# power_electronicsV4_3.net
KiCad netlist of a schematic drawn in EAGLE
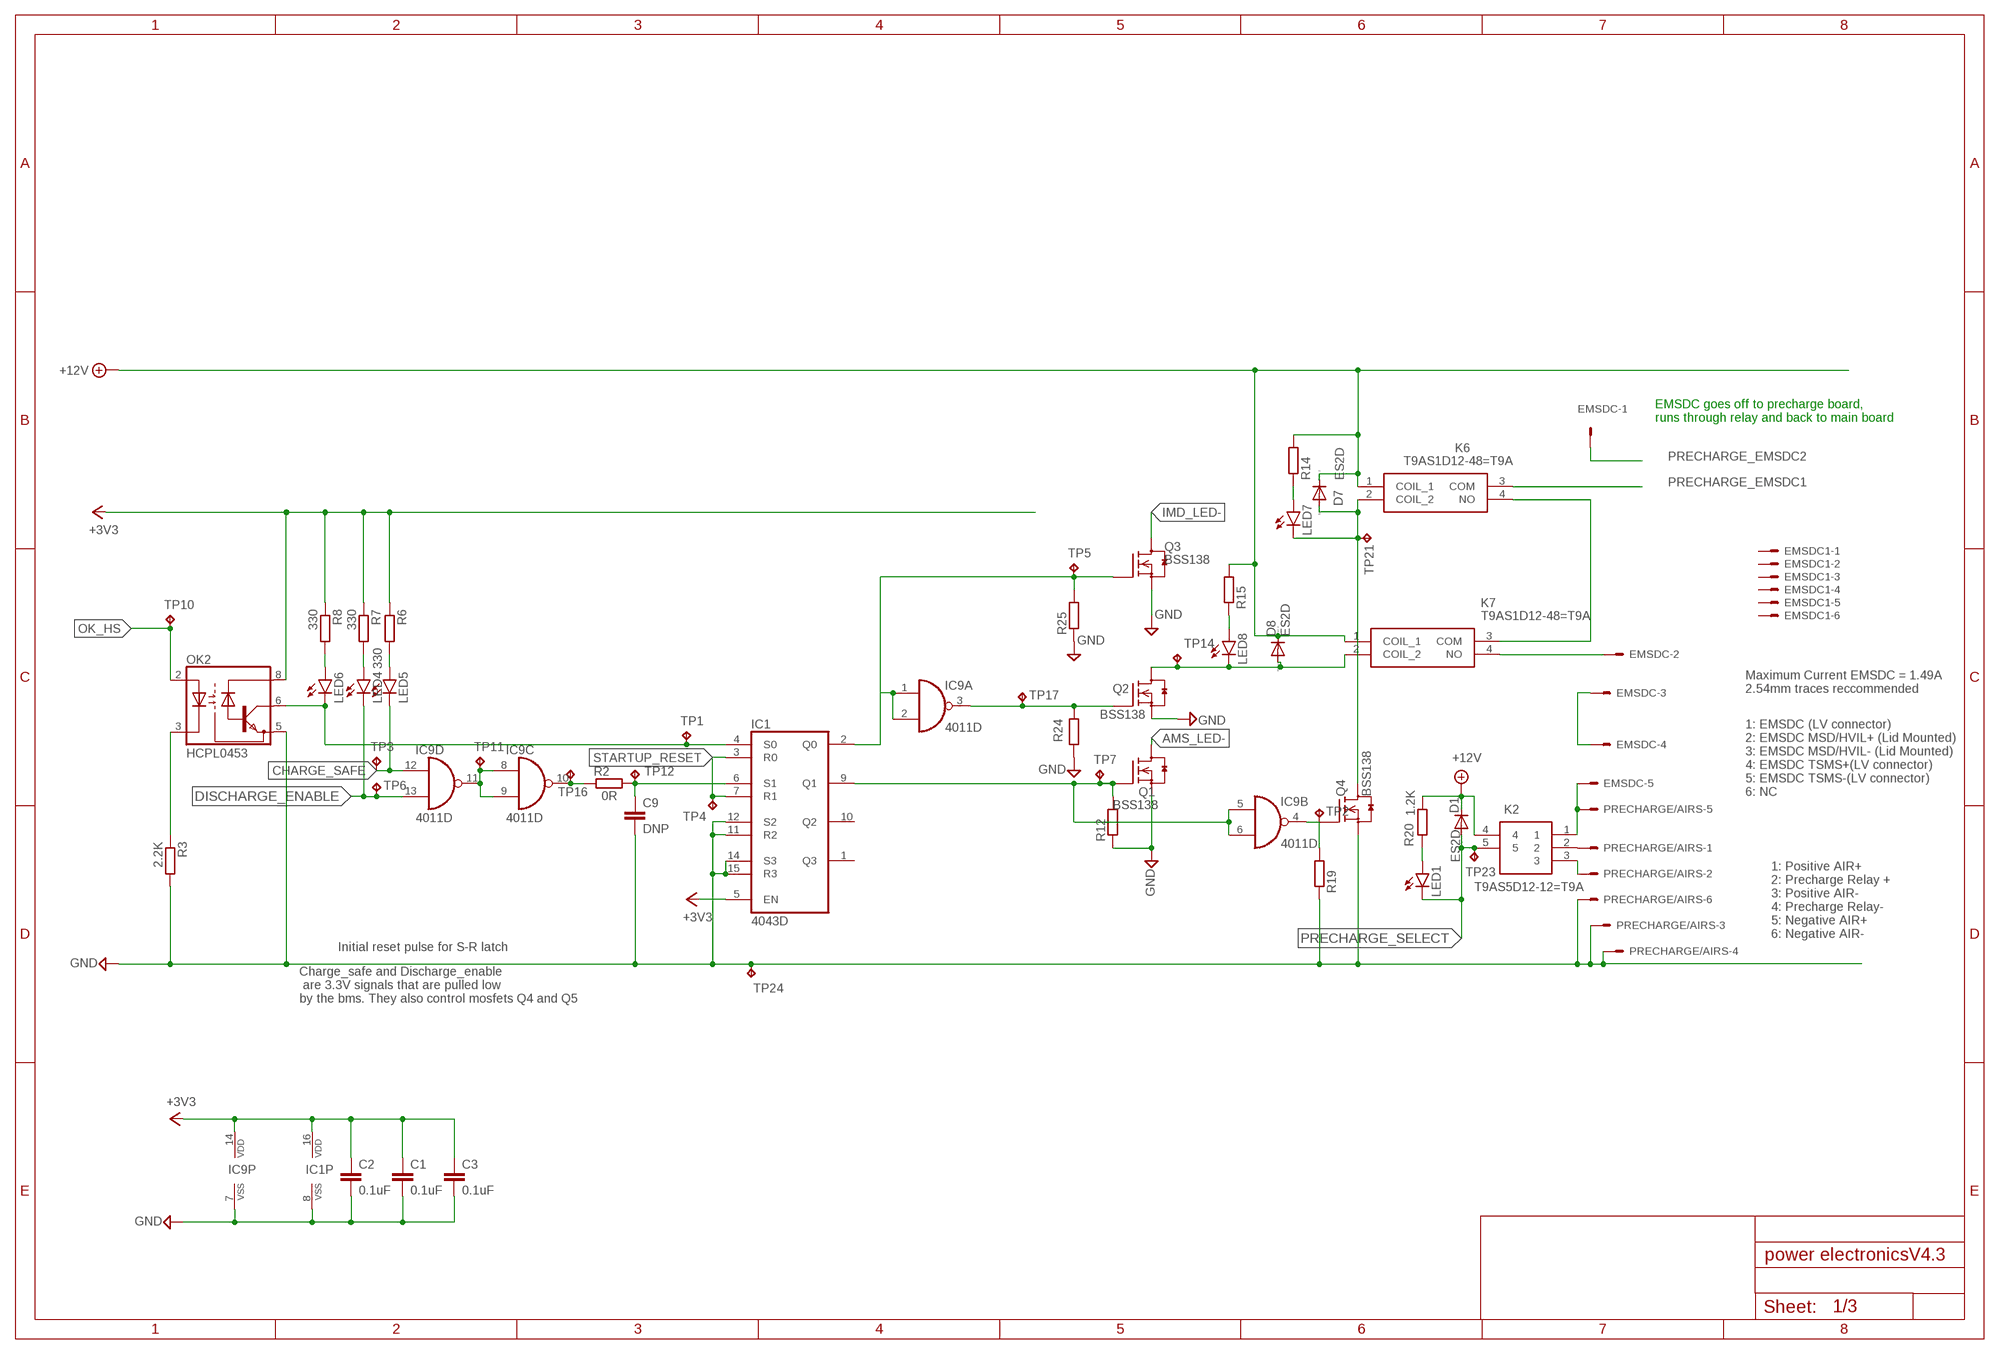
[diagram p0: schematic, sheet 1]
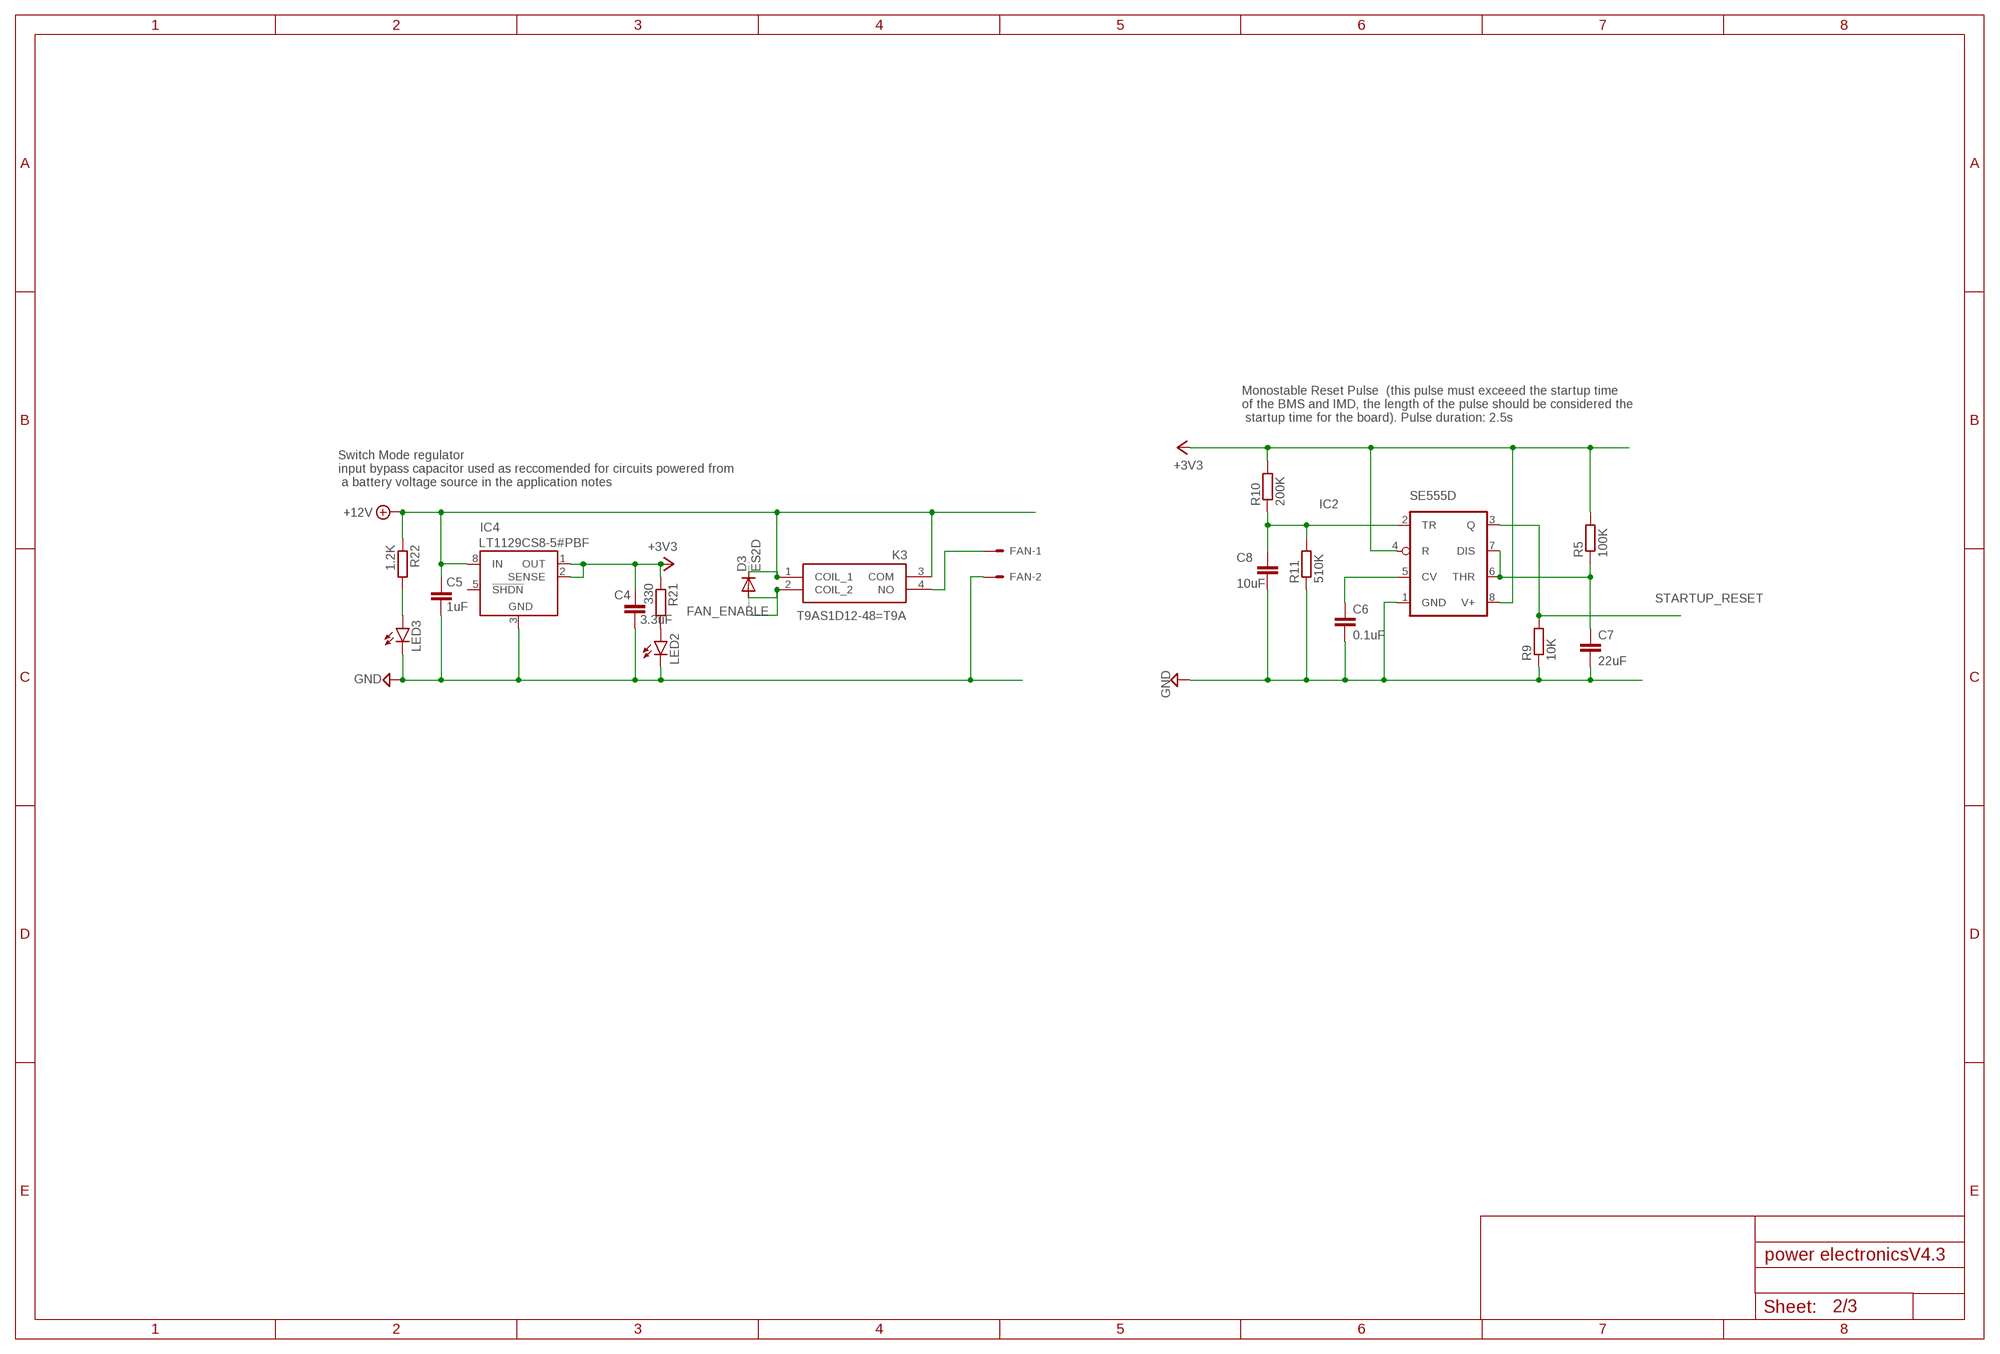
[diagram p1: schematic, sheet 2]
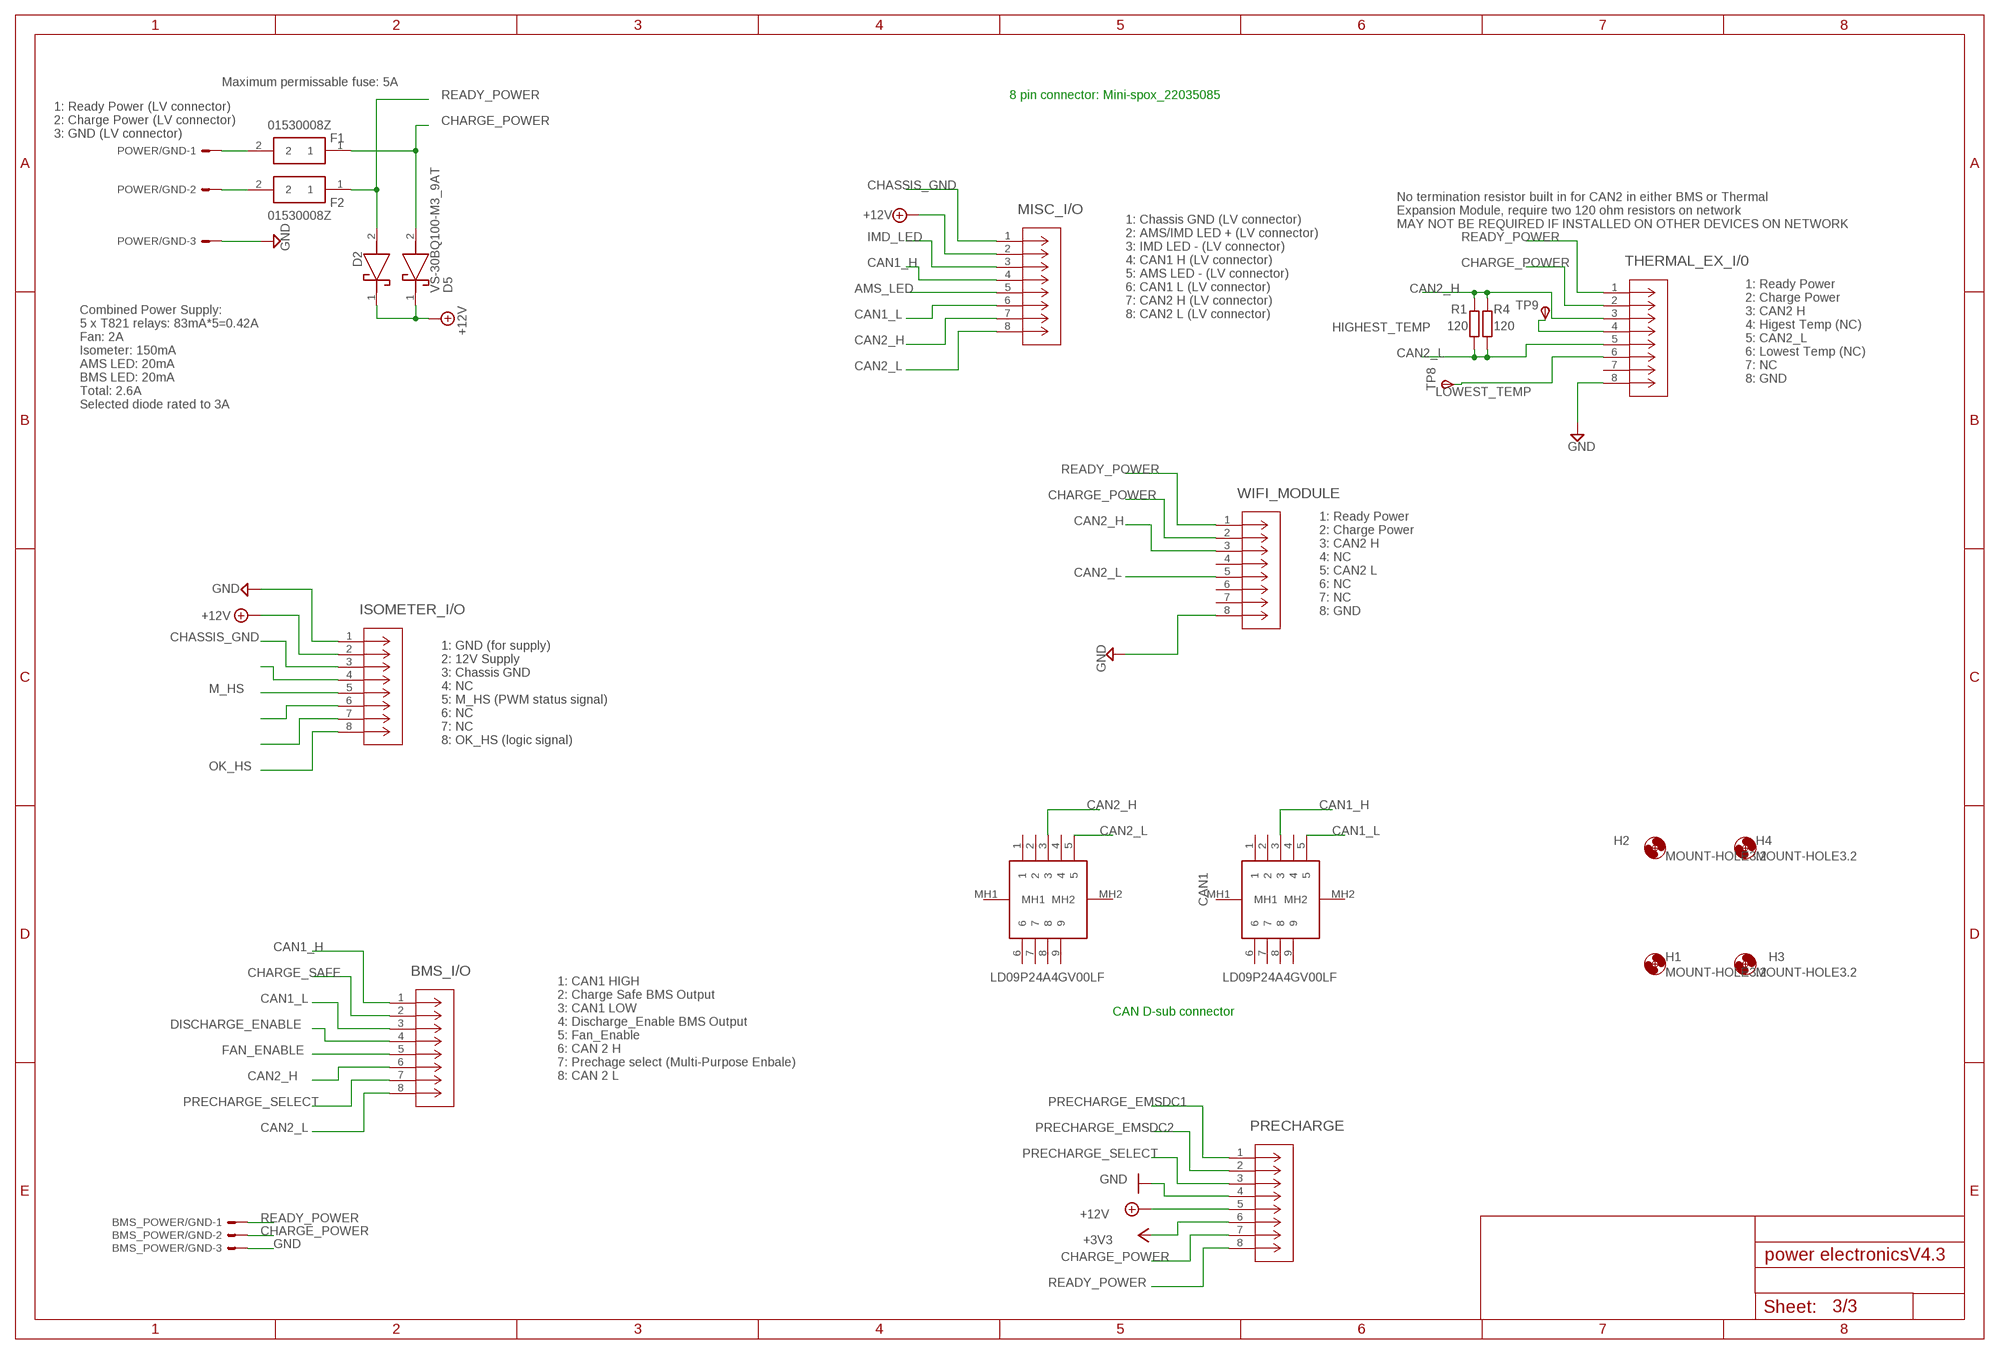
[diagram p2: schematic, sheet 3]

(export (version "E")
  (design (tool "Eeschema 10.0.6"))
  (components
    (comp (ref "C4")
      (value "3.3uF")
      (footprint "eagle-import:C0805")
      (libsource (lib "eagle-import") (part "C-EUC0805"))
    )
    (comp (ref "C5")
      (value "1uF")
      (footprint "eagle-import:C0805")
      (libsource (lib "eagle-import") (part "C-EUC0805"))
    )
    (comp (ref "C6")
      (value "0.1uF")
      (footprint "eagle-import:C0805")
      (libsource (lib "eagle-import") (part "C-EUC0805"))
    )
    (comp (ref "C7")
      (value "22uF")
      (footprint "eagle-import:C1206")
      (libsource (lib "eagle-import") (part "C-EUC1206"))
    )
    (comp (ref "C8")
      (value "10uF")
      (footprint "eagle-import:C0805")
      (libsource (lib "eagle-import") (part "C-EUC0805"))
    )
    (comp (ref "D3")
      (value "ES2D")
      (footprint "eagle-import:SMB")
      (libsource (lib "eagle-import") (part "ES2D"))
    )
    (comp (ref "FAN")
      (value "KK-156-2")
      (footprint "eagle-import:KK-156-2")
      (fields (field (name "MF") "MOLEX"))
      (libsource (lib "eagle-import") (part "KK-156-2"))
    )
    (comp (ref "IC2")
      (value "SE555D")
      (footprint "eagle-import:SO08")
      (libsource (lib "eagle-import") (part "555DSE"))
    )
    (comp (ref "IC4")
      (value "LT1129CS8")
      (footprint "eagle-import:SOIC8")
      (fields (field (name "MPN") "LT1129CS8-5#PBF"))
      (libsource (lib "eagle-import") (part "LT1129CS8"))
    )
    (comp (ref "K3")
      (value "T9AS1D12-48=T9A")
      (footprint "eagle-import:T9AS1D1248T9A")
      (fields (field (name "RS_PART_NUMBER") "6802534P"))
      (libsource (lib "eagle-import") (part "T9AS1D12-48=T9A"))
    )
    (comp (ref "LED2")
      (value "LEDSML0805")
      (footprint "eagle-import:SML0805")
      (libsource (lib "eagle-import") (part "LEDSML0805"))
    )
    (comp (ref "LED3")
      (value "LEDSML0805")
      (footprint "eagle-import:SML0805")
      (libsource (lib "eagle-import") (part "LEDSML0805"))
    )
    (comp (ref "R5")
      (value "100K")
      (footprint "eagle-import:R0805")
      (libsource (lib "eagle-import") (part "R-EU_R0805"))
    )
    (comp (ref "R9")
      (value "10K")
      (footprint "eagle-import:R0805")
      (libsource (lib "eagle-import") (part "R-EU_R0805"))
    )
    (comp (ref "R10")
      (value "200K")
      (footprint "eagle-import:R0805")
      (libsource (lib "eagle-import") (part "R-EU_R0805"))
    )
    (comp (ref "R11")
      (value "510K")
      (footprint "eagle-import:R0805")
      (libsource (lib "eagle-import") (part "R-EU_R0805"))
    )
    (comp (ref "R21")
      (value "330")
      (footprint "eagle-import:R0805")
      (libsource (lib "eagle-import") (part "R-EU_R0805"))
    )
    (comp (ref "R22")
      (value "1.2K")
      (footprint "eagle-import:R0805")
      (libsource (lib "eagle-import") (part "R-EU_R0805"))
    )
    (comp (ref "C1")
      (value "0.1uF")
      (footprint "eagle-import:C0805")
      (libsource (lib "eagle-import") (part "C-EUC0805"))
    )
    (comp (ref "C2")
      (value "0.1uF")
      (footprint "eagle-import:C0805")
      (libsource (lib "eagle-import") (part "C-EUC0805"))
    )
    (comp (ref "C3")
      (value "0.1uF")
      (footprint "eagle-import:C0805")
      (libsource (lib "eagle-import") (part "C-EUC0805"))
    )
    (comp (ref "C9")
      (value "DNP")
      (footprint "eagle-import:C0805K")
      (libsource (lib "eagle-import") (part "C-EUC0805K"))
    )
    (comp (ref "D1")
      (value "ES2D")
      (footprint "eagle-import:SMB")
      (libsource (lib "eagle-import") (part "ES2D"))
    )
    (comp (ref "D7")
      (value "ES2D")
      (footprint "eagle-import:SMB")
      (libsource (lib "eagle-import") (part "ES2D"))
    )
    (comp (ref "D8")
      (value "ES2D")
      (footprint "eagle-import:SMB")
      (libsource (lib "eagle-import") (part "ES2D"))
    )
    (comp (ref "EMSDC")
      (value "KK-156-6")
      (footprint "eagle-import:KK-156-6")
      (fields (field (name "MF") "MOLEX"))
      (libsource (lib "eagle-import") (part "KK-156-6"))
    )
    (comp (ref "EMSDC1")
      (value "KK-156-6")
      (footprint "eagle-import:KK-156-6")
      (fields (field (name "MF") "MOLEX"))
      (libsource (lib "eagle-import") (part "KK-156-6"))
    )
    (comp (ref "IC1")
      (value "4043D")
      (footprint "eagle-import:SO16")
      (libsource (lib "eagle-import") (part "4043D"))
    )
    (comp (ref "IC9")
      (value "4011D")
      (footprint "eagle-import:SO14")
      (libsource (lib "eagle-import") (part "4011D"))
    )
    (comp (ref "K2")
      (value "T9AS5D12-12=T9A")
      (footprint "eagle-import:T9AS1D12")
      (fields (field (name "RS_PART_NUMBER") "6802528"))
      (libsource (lib "eagle-import") (part "T9AS5D12-12=T9A"))
    )
    (comp (ref "K6")
      (value "T9AS1D12-48=T9A")
      (footprint "eagle-import:T9AS1D1248T9A")
      (libsource (lib "eagle-import") (part "T9AS1D12-12=T9A_T9AS1D12-48=T9A"))
    )
    (comp (ref "K7")
      (value "T9AS1D12-48=T9A")
      (footprint "eagle-import:T9AS1D1248T9A")
      (libsource (lib "eagle-import") (part "T9AS1D12-12=T9A_T9AS1D12-48=T9A"))
    )
    (comp (ref "LED1")
      (value "LEDSML0805")
      (footprint "eagle-import:SML0805")
      (libsource (lib "eagle-import") (part "LEDSML0805"))
    )
    (comp (ref "LED4")
      (value "LEDSML0805")
      (footprint "eagle-import:SML0805")
      (libsource (lib "eagle-import") (part "LEDSML0805"))
    )
    (comp (ref "LED5")
      (value "LEDSML0805")
      (footprint "eagle-import:SML0805")
      (libsource (lib "eagle-import") (part "LEDSML0805"))
    )
    (comp (ref "LED6")
      (value "LEDSML0805")
      (footprint "eagle-import:SML0805")
      (libsource (lib "eagle-import") (part "LEDSML0805"))
    )
    (comp (ref "LED7")
      (value "LEDSML0805")
      (footprint "eagle-import:SML0805")
      (libsource (lib "eagle-import") (part "LEDSML0805"))
    )
    (comp (ref "LED8")
      (value "LEDSML0805")
      (footprint "eagle-import:SML0805")
      (libsource (lib "eagle-import") (part "LEDSML0805"))
    )
    (comp (ref "OK2")
      (value "HCPL0453")
      (footprint "eagle-import:SOIC08")
      (fields (field (name "MF") "AGILENT TECHNOLOGIES") (field (name "MPN") "HCPL-0453-000E"))
      (libsource (lib "eagle-import") (part "HCPL0453"))
    )
    (comp (ref "PRECHARGE/AIRS")
      (value "KK-156-6")
      (footprint "eagle-import:KK-156-6")
      (fields (field (name "MF") "MOLEX"))
      (libsource (lib "eagle-import") (part "KK-156-6"))
    )
    (comp (ref "Q1")
      (value "BSS138")
      (footprint "eagle-import:SOT23")
      (libsource (lib "eagle-import") (part "BSS138"))
    )
    (comp (ref "Q2")
      (value "BSS138")
      (footprint "eagle-import:SOT23")
      (libsource (lib "eagle-import") (part "BSS138"))
    )
    (comp (ref "Q3")
      (value "BSS138")
      (footprint "eagle-import:SOT23")
      (libsource (lib "eagle-import") (part "BSS138"))
    )
    (comp (ref "Q4")
      (value "BSS138")
      (footprint "eagle-import:SOT23")
      (libsource (lib "eagle-import") (part "BSS138"))
    )
    (comp (ref "R2")
      (value "0R")
      (footprint "eagle-import:R0805")
      (libsource (lib "eagle-import") (part "R-EU_R0805"))
    )
    (comp (ref "R3")
      (value "2.2K")
      (footprint "eagle-import:R0805")
      (libsource (lib "eagle-import") (part "R-EU_R0805"))
    )
    (comp (ref "R6")
      (value "330")
      (footprint "eagle-import:R0805")
      (libsource (lib "eagle-import") (part "R-EU_R0805"))
    )
    (comp (ref "R7")
      (value "330")
      (footprint "eagle-import:R0805")
      (libsource (lib "eagle-import") (part "R-EU_R0805"))
    )
    (comp (ref "R8")
      (value "330")
      (footprint "eagle-import:R0805")
      (libsource (lib "eagle-import") (part "R-EU_R0805"))
    )
    (comp (ref "R12")
      (value "R-EU_R0805")
      (footprint "eagle-import:R0805")
      (libsource (lib "eagle-import") (part "R-EU_R0805"))
    )
    (comp (ref "R14")
      (value "R-EU_R0805")
      (footprint "eagle-import:R0805")
      (libsource (lib "eagle-import") (part "R-EU_R0805"))
    )
    (comp (ref "R15")
      (value "R-EU_R0805")
      (footprint "eagle-import:R0805")
      (libsource (lib "eagle-import") (part "R-EU_R0805"))
    )
    (comp (ref "R19")
      (value "R-EU_R0805")
      (footprint "eagle-import:R0805")
      (libsource (lib "eagle-import") (part "R-EU_R0805"))
    )
    (comp (ref "R20")
      (value "1.2K")
      (footprint "eagle-import:R0805")
      (libsource (lib "eagle-import") (part "R-EU_R0805"))
    )
    (comp (ref "R24")
      (value "R-EU_R0805")
      (footprint "eagle-import:R0805")
      (libsource (lib "eagle-import") (part "R-EU_R0805"))
    )
    (comp (ref "R25")
      (value "R-EU_R0805")
      (footprint "eagle-import:R0805")
      (libsource (lib "eagle-import") (part "R-EU_R0805"))
    )
    (comp (ref "TP1")
      (value "TPPAD1-17")
      (footprint "eagle-import:P1-17")
      (libsource (lib "eagle-import") (part "TPPAD1-17"))
    )
    (comp (ref "TP2")
      (value "TPPAD1-17")
      (footprint "eagle-import:P1-17")
      (libsource (lib "eagle-import") (part "TPPAD1-17"))
    )
    (comp (ref "TP3")
      (value "TPPAD1-17")
      (footprint "eagle-import:P1-17")
      (libsource (lib "eagle-import") (part "TPPAD1-17"))
    )
    (comp (ref "TP4")
      (value "TPPAD1-17")
      (footprint "eagle-import:P1-17")
      (libsource (lib "eagle-import") (part "TPPAD1-17"))
    )
    (comp (ref "TP5")
      (value "TPPAD1-17")
      (footprint "eagle-import:P1-17")
      (libsource (lib "eagle-import") (part "TPPAD1-17"))
    )
    (comp (ref "TP6")
      (value "TPPAD1-17")
      (footprint "eagle-import:P1-17")
      (libsource (lib "eagle-import") (part "TPPAD1-17"))
    )
    (comp (ref "TP7")
      (value "TPPAD1-17")
      (footprint "eagle-import:P1-17")
      (libsource (lib "eagle-import") (part "TPPAD1-17"))
    )
    (comp (ref "TP10")
      (value "TPPAD1-17")
      (footprint "eagle-import:P1-17")
      (libsource (lib "eagle-import") (part "TPPAD1-17"))
    )
    (comp (ref "TP11")
      (value "TPPAD1-17")
      (footprint "eagle-import:P1-17")
      (libsource (lib "eagle-import") (part "TPPAD1-17"))
    )
    (comp (ref "TP12")
      (value "TPPAD1-17")
      (footprint "eagle-import:P1-17")
      (libsource (lib "eagle-import") (part "TPPAD1-17"))
    )
    (comp (ref "TP14")
      (value "TPPAD1-17")
      (footprint "eagle-import:P1-17")
      (libsource (lib "eagle-import") (part "TPPAD1-17"))
    )
    (comp (ref "TP16")
      (value "TPPAD1-17")
      (footprint "eagle-import:P1-17")
      (libsource (lib "eagle-import") (part "TPPAD1-17"))
    )
    (comp (ref "TP17")
      (value "TPPAD1-17")
      (footprint "eagle-import:P1-17")
      (libsource (lib "eagle-import") (part "TPPAD1-17"))
    )
    (comp (ref "TP21")
      (value "TPPAD1-17")
      (footprint "eagle-import:P1-17")
      (libsource (lib "eagle-import") (part "TPPAD1-17"))
    )
    (comp (ref "TP23")
      (value "TPPAD1-17")
      (footprint "eagle-import:P1-17")
      (libsource (lib "eagle-import") (part "TPPAD1-17"))
    )
    (comp (ref "TP24")
      (value "TPPAD1-17")
      (footprint "eagle-import:P1-17")
      (libsource (lib "eagle-import") (part "TPPAD1-17"))
    )
    (comp (ref "BMS_I/O")
      (value "MINI-SPOX_22035085")
      (footprint "eagle-import:CON_22035085_MOL")
      (fields
        (field (name "MANUFACTURER_PART_NUMBER") "22035085")
        (field (name "COPYRIGHT") "Copyright (C) 2023 Ultra Librarian. All rights reserved.")
      )
      (libsource (lib "eagle-import") (part "MINI-SPOX_22035085"))
    )
    (comp (ref "BMS_POWER/GND")
      (value "KK-156-3")
      (footprint "eagle-import:KK-156-3")
      (fields (field (name "MF") "MOLEX"))
      (libsource (lib "eagle-import") (part "KK-156-3"))
    )
    (comp (ref "CAN1")
      (value "LD09P24A4GV00LF")
      (footprint "eagle-import:LD09P24A4GV00LF")
      (fields (field (name "MOUSER_PART_NUMBER") "649-LD09P24A4GV00LF"))
      (libsource (lib "eagle-import") (part "LD09P24A4GV00LF"))
    )
    (comp (ref "CAN2")
      (value "LD09P24A4GV00LF")
      (footprint "eagle-import:LD09P24A4GV00LF")
      (fields (field (name "MOUSER_PART_NUMBER") "649-LD09P24A4GV00LF"))
      (libsource (lib "eagle-import") (part "LD09P24A4GV00LF"))
    )
    (comp (ref "D2")
      (value "VS-30BQ100-M3_9AT")
      (footprint "eagle-import:DIOM7959X262N")
      (fields
        (field (name "MANUFACTURER_PART_NUMBER") "VS-30BQ100-M3/9AT")
        (field (name "MOUSER_PART_NUMBER") "78-VS-30BQ100-M39AT")
      )
      (libsource (lib "eagle-import") (part "VS-30BQ100-M3_9AT"))
    )
    (comp (ref "D5")
      (value "VS-30BQ100-M3_9AT")
      (footprint "eagle-import:DIOM7959X262N")
      (fields
        (field (name "MANUFACTURER_PART_NUMBER") "VS-30BQ100-M3/9AT")
        (field (name "MOUSER_PART_NUMBER") "78-VS-30BQ100-M39AT")
      )
      (libsource (lib "eagle-import") (part "VS-30BQ100-M3_9AT"))
    )
    (comp (ref "F1")
      (value "01530008Z")
      (footprint "eagle-import:01530008")
      (fields (field (name "RS_PART_NUMBER") "3607317"))
      (libsource (lib "eagle-import") (part "01530008Z"))
    )
    (comp (ref "F2")
      (value "01530008Z")
      (footprint "eagle-import:01530008")
      (fields (field (name "RS_PART_NUMBER") "3607317"))
      (libsource (lib "eagle-import") (part "01530008Z"))
    )
    (comp (ref "H1")
      (value "MOUNT-HOLE3.2")
      (footprint "eagle-import:3,2")
      (libsource (lib "eagle-import") (part "MOUNT-HOLE3.2"))
    )
    (comp (ref "H2")
      (value "MOUNT-HOLE3.2")
      (footprint "eagle-import:3,2")
      (libsource (lib "eagle-import") (part "MOUNT-HOLE3.2"))
    )
    (comp (ref "H3")
      (value "MOUNT-HOLE3.2")
      (footprint "eagle-import:3,2")
      (libsource (lib "eagle-import") (part "MOUNT-HOLE3.2"))
    )
    (comp (ref "H4")
      (value "MOUNT-HOLE3.2")
      (footprint "eagle-import:3,2")
      (libsource (lib "eagle-import") (part "MOUNT-HOLE3.2"))
    )
    (comp (ref "ISOMETER_I/O")
      (value "MINI-SPOX_22035085")
      (footprint "eagle-import:CON_22035085_MOL")
      (fields
        (field (name "MANUFACTURER_PART_NUMBER") "22035085")
        (field (name "COPYRIGHT") "Copyright (C) 2023 Ultra Librarian. All rights reserved.")
      )
      (libsource (lib "eagle-import") (part "MINI-SPOX_22035085"))
    )
    (comp (ref "MISC_I/O")
      (value "MINI-SPOX_22035085")
      (footprint "eagle-import:CON_22035085_MOL")
      (fields
        (field (name "MANUFACTURER_PART_NUMBER") "22035085")
        (field (name "COPYRIGHT") "Copyright (C) 2023 Ultra Librarian. All rights reserved.")
      )
      (libsource (lib "eagle-import") (part "MINI-SPOX_22035085"))
    )
    (comp (ref "POWER/GND")
      (value "KK-156-3")
      (footprint "eagle-import:KK-156-3")
      (fields (field (name "MF") "MOLEX"))
      (libsource (lib "eagle-import") (part "KK-156-3"))
    )
    (comp (ref "PRECHARGE")
      (value "MINI-SPOX_22035085")
      (footprint "eagle-import:CON_22035085_MOL")
      (fields
        (field (name "MANUFACTURER_PART_NUMBER") "22035085")
        (field (name "COPYRIGHT") "Copyright (C) 2023 Ultra Librarian. All rights reserved.")
      )
      (libsource (lib "eagle-import") (part "MINI-SPOX_22035085"))
    )
    (comp (ref "R1")
      (value "120")
      (footprint "eagle-import:R1206")
      (libsource (lib "eagle-import") (part "R-EU_R1206"))
    )
    (comp (ref "R4")
      (value "120")
      (footprint "eagle-import:R1206")
      (libsource (lib "eagle-import") (part "R-EU_R1206"))
    )
    (comp (ref "THERMAL_EX_I/0")
      (value "MINI-SPOX_22035085")
      (footprint "eagle-import:CON_22035085_MOL")
      (fields
        (field (name "MANUFACTURER_PART_NUMBER") "22035085")
        (field (name "COPYRIGHT") "Copyright (C) 2023 Ultra Librarian. All rights reserved.")
      )
      (libsource (lib "eagle-import") (part "MINI-SPOX_22035085"))
    )
    (comp (ref "TP8")
      (value "TPSTP11R")
      (footprint "eagle-import:TP11R")
      (libsource (lib "eagle-import") (part "TPSTP11R"))
    )
    (comp (ref "TP9")
      (value "TPSTP11R")
      (footprint "eagle-import:TP11R")
      (libsource (lib "eagle-import") (part "TPSTP11R"))
    )
    (comp (ref "WIFI_MODULE")
      (value "MINI-SPOX_22035085")
      (footprint "eagle-import:CON_22035085_MOL")
      (fields
        (field (name "MANUFACTURER_PART_NUMBER") "22035085")
        (field (name "COPYRIGHT") "Copyright (C) 2023 Ultra Librarian. All rights reserved.")
      )
      (libsource (lib "eagle-import") (part "MINI-SPOX_22035085"))
    )
  )
  (nets
    (net (code "1") (name "+3V3") (class "Default")
      (node (ref "C1") (pin "1") (pinfunction "1_1") (pintype "passive"))
      (node (ref "C2") (pin "1") (pinfunction "1_1") (pintype "passive"))
      (node (ref "C3") (pin "1") (pinfunction "1_1") (pintype "passive"))
      (node (ref "C4") (pin "1") (pinfunction "1_1") (pintype "passive"))
      (node (ref "IC1") (pin "16") (pinfunction "VDD_16") (pintype "power_in"))
      (node (ref "IC1") (pin "5") (pinfunction "EN_5") (pintype "input"))
      (node (ref "IC2") (pin "4") (pinfunction "R_4") (pintype "input"))
      (node (ref "IC2") (pin "8") (pinfunction "V+_8") (pintype "power_in"))
      (node (ref "IC4") (pin "1") (pinfunction "OUT_1") (pintype "output"))
      (node (ref "IC4") (pin "2") (pinfunction "SENSE_2") (pintype "input"))
      (node (ref "IC9") (pin "14") (pinfunction "VDD_14") (pintype "power_in"))
      (node (ref "OK2") (pin "8") (pinfunction "VCC_8") (pintype "passive"))
      (node (ref "PRECHARGE") (pin "6") (pinfunction "6_6") (pintype "passive"))
      (node (ref "R10") (pin "2") (pinfunction "2_2") (pintype "passive"))
      (node (ref "R21") (pin "1") (pinfunction "1_1") (pintype "passive"))
      (node (ref "R5") (pin "2") (pinfunction "2_2") (pintype "passive"))
      (node (ref "R6") (pin "1") (pinfunction "1_1") (pintype "passive"))
      (node (ref "R7") (pin "1") (pinfunction "1_1") (pintype "passive"))
      (node (ref "R8") (pin "1") (pinfunction "1_1") (pintype "passive"))
    )
    (net (code "2") (name "+12V") (class "Default")
      (node (ref "C5") (pin "1") (pinfunction "1_1") (pintype "passive"))
      (node (ref "D1") (pin "C") (pinfunction "C_C") (pintype "passive"))
      (node (ref "D2") (pin "1") (pinfunction "K_1") (pintype "bidirectional"))
      (node (ref "D3") (pin "C") (pinfunction "C_C") (pintype "passive"))
      (node (ref "D5") (pin "1") (pinfunction "K_1") (pintype "bidirectional"))
      (node (ref "D7") (pin "C") (pinfunction "C_C") (pintype "passive"))
      (node (ref "D8") (pin "C") (pinfunction "C_C") (pintype "passive"))
      (node (ref "IC4") (pin "8") (pinfunction "IN_8") (pintype "input"))
      (node (ref "ISOMETER_I/O") (pin "2") (pinfunction "2_2") (pintype "passive"))
      (node (ref "K2") (pin "4") (pinfunction "4_4") (pintype "bidirectional"))
      (node (ref "K3") (pin "1") (pinfunction "COIL_1_1") (pintype "bidirectional"))
      (node (ref "K3") (pin "3") (pinfunction "COM_3") (pintype "bidirectional"))
      (node (ref "K6") (pin "1") (pinfunction "COIL_1_1") (pintype "bidirectional"))
      (node (ref "K7") (pin "1") (pinfunction "COIL_1_1") (pintype "bidirectional"))
      (node (ref "MISC_I/O") (pin "2") (pinfunction "2_2") (pintype "passive"))
      (node (ref "PRECHARGE") (pin "5") (pinfunction "5_5") (pintype "passive"))
      (node (ref "R14") (pin "2") (pinfunction "2_2") (pintype "passive"))
      (node (ref "R15") (pin "2") (pinfunction "2_2") (pintype "passive"))
      (node (ref "R20") (pin "1") (pinfunction "1_1") (pintype "passive"))
      (node (ref "R22") (pin "1") (pinfunction "1_1") (pintype "passive"))
    )
    (net (code "3") (name "AMS_LED") (class "Default")
      (node (ref "MISC_I/O") (pin "5") (pinfunction "5_5") (pintype "passive"))
    )
    (net (code "4") (name "AMS_LED-") (class "Default")
      (node (ref "Q1") (pin "3") (pinfunction "D_3") (pintype "passive"))
    )
    (net (code "5") (name "CAN1_H") (class "Default")
      (node (ref "BMS_I/O") (pin "1") (pinfunction "1_1") (pintype "passive"))
      (node (ref "CAN1") (pin "3") (pinfunction "3_3") (pintype "bidirectional"))
      (node (ref "MISC_I/O") (pin "4") (pinfunction "4_4") (pintype "passive"))
    )
    (net (code "6") (name "CAN1_L") (class "Default")
      (node (ref "BMS_I/O") (pin "3") (pinfunction "3_3") (pintype "passive"))
      (node (ref "CAN1") (pin "5") (pinfunction "5_5") (pintype "bidirectional"))
      (node (ref "MISC_I/O") (pin "6") (pinfunction "6_6") (pintype "passive"))
    )
    (net (code "7") (name "CAN2_H") (class "Default")
      (node (ref "BMS_I/O") (pin "6") (pinfunction "6_6") (pintype "passive"))
      (node (ref "CAN2") (pin "3") (pinfunction "3_3") (pintype "bidirectional"))
      (node (ref "MISC_I/O") (pin "7") (pinfunction "7_7") (pintype "passive"))
      (node (ref "R1") (pin "1") (pinfunction "1_1") (pintype "passive"))
      (node (ref "R4") (pin "1") (pinfunction "1_1") (pintype "passive"))
      (node (ref "THERMAL_EX_I/0") (pin "3") (pinfunction "3_3") (pintype "passive"))
      (node (ref "WIFI_MODULE") (pin "3") (pinfunction "3_3") (pintype "passive"))
    )
    (net (code "8") (name "CAN2_L") (class "Default")
      (node (ref "BMS_I/O") (pin "8") (pinfunction "8_8") (pintype "passive"))
      (node (ref "CAN2") (pin "5") (pinfunction "5_5") (pintype "bidirectional"))
      (node (ref "MISC_I/O") (pin "8") (pinfunction "8_8") (pintype "passive"))
      (node (ref "R1") (pin "2") (pinfunction "2_2") (pintype "passive"))
      (node (ref "R4") (pin "2") (pinfunction "2_2") (pintype "passive"))
      (node (ref "THERMAL_EX_I/0") (pin "5") (pinfunction "5_5") (pintype "passive"))
      (node (ref "WIFI_MODULE") (pin "5") (pinfunction "5_5") (pintype "passive"))
    )
    (net (code "9") (name "CHARGE_POWER") (class "Default")
      (node (ref "BMS_POWER/GND") (pin "2") (pinfunction "S_2") (pintype "passive"))
      (node (ref "D5") (pin "2") (pinfunction "A_2") (pintype "bidirectional"))
      (node (ref "F1") (pin "1") (pinfunction "1_1") (pintype "bidirectional"))
      (node (ref "PRECHARGE") (pin "7") (pinfunction "7_7") (pintype "passive"))
      (node (ref "THERMAL_EX_I/0") (pin "2") (pinfunction "2_2") (pintype "passive"))
      (node (ref "WIFI_MODULE") (pin "2") (pinfunction "2_2") (pintype "passive"))
    )
    (net (code "10") (name "CHARGE_SAFE") (class "Default")
      (node (ref "BMS_I/O") (pin "2") (pinfunction "2_2") (pintype "passive"))
      (node (ref "IC9") (pin "12") (pinfunction "I0_12") (pintype "input"))
      (node (ref "LED5") (pin "C") (pinfunction "C_C") (pintype "passive"))
      (node (ref "TP3") (pin "TP") (pinfunction "TP_TP") (pintype "input"))
    )
    (net (code "11") (name "CHASSIS_GND") (class "Default")
      (node (ref "ISOMETER_I/O") (pin "3") (pinfunction "3_3") (pintype "passive"))
      (node (ref "MISC_I/O") (pin "1") (pinfunction "1_1") (pintype "passive"))
    )
    (net (code "12") (name "DISCHARGE_ENABLE") (class "Default")
      (node (ref "BMS_I/O") (pin "4") (pinfunction "4_4") (pintype "passive"))
      (node (ref "IC1") (pin "9") (pinfunction "Q1_9") (pintype "output"))
      (node (ref "IC9") (pin "13") (pinfunction "I1_13") (pintype "input"))
      (node (ref "IC9") (pin "5") (pinfunction "I0_5") (pintype "input"))
      (node (ref "IC9") (pin "6") (pinfunction "I1_6") (pintype "input"))
      (node (ref "LED4") (pin "C") (pinfunction "C_C") (pintype "passive"))
      (node (ref "Q1") (pin "1") (pinfunction "G_1") (pintype "passive"))
      (node (ref "R12") (pin "2") (pinfunction "2_2") (pintype "passive"))
      (node (ref "TP6") (pin "TP") (pinfunction "TP_TP") (pintype "input"))
      (node (ref "TP7") (pin "TP") (pinfunction "TP_TP") (pintype "input"))
    )
    (net (code "13") (name "FAN_ENABLE") (class "Default")
      (node (ref "BMS_I/O") (pin "5") (pinfunction "5_5") (pintype "passive"))
      (node (ref "D3") (pin "A") (pinfunction "A_A") (pintype "passive"))
      (node (ref "K3") (pin "2") (pinfunction "COIL_2_2") (pintype "bidirectional"))
    )
    (net (code "14") (name "GND") (class "Default")
      (node (ref "BMS_POWER/GND") (pin "3") (pinfunction "S_3") (pintype "passive"))
      (node (ref "C1") (pin "2") (pinfunction "2_2") (pintype "passive"))
      (node (ref "C2") (pin "2") (pinfunction "2_2") (pintype "passive"))
      (node (ref "C3") (pin "2") (pinfunction "2_2") (pintype "passive"))
      (node (ref "C4") (pin "2") (pinfunction "2_2") (pintype "passive"))
      (node (ref "C5") (pin "2") (pinfunction "2_2") (pintype "passive"))
      (node (ref "C6") (pin "2") (pinfunction "2_2") (pintype "passive"))
      (node (ref "C7") (pin "2") (pinfunction "2_2") (pintype "passive"))
      (node (ref "C8") (pin "2") (pinfunction "2_2") (pintype "passive"))
      (node (ref "C9") (pin "2") (pinfunction "2_2") (pintype "passive"))
      (node (ref "FAN") (pin "2") (pinfunction "S_2") (pintype "passive"))
      (node (ref "IC1") (pin "11") (pinfunction "R2_11") (pintype "input"))
      (node (ref "IC1") (pin "12") (pinfunction "S2_12") (pintype "input"))
      (node (ref "IC1") (pin "14") (pinfunction "S3_14") (pintype "input"))
      (node (ref "IC1") (pin "15") (pinfunction "R3_15") (pintype "input"))
      (node (ref "IC1") (pin "8") (pinfunction "VSS_8") (pintype "power_in"))
      (node (ref "IC2") (pin "1") (pinfunction "GND_1") (pintype "power_in"))
      (node (ref "IC4") (pin "3") (pinfunction "GND_3") (pintype "power_in"))
      (node (ref "IC9") (pin "7") (pinfunction "VSS_7") (pintype "power_in"))
      (node (ref "ISOMETER_I/O") (pin "1") (pinfunction "1_1") (pintype "passive"))
      (node (ref "LED2") (pin "C") (pinfunction "C_C") (pintype "passive"))
      (node (ref "LED3") (pin "C") (pinfunction "C_C") (pintype "passive"))
      (node (ref "OK2") (pin "5") (pinfunction "GND_5") (pintype "passive"))
      (node (ref "POWER/GND") (pin "3") (pinfunction "S_3") (pintype "passive"))
      (node (ref "PRECHARGE") (pin "4") (pinfunction "4_4") (pintype "passive"))
      (node (ref "PRECHARGE/AIRS") (pin "3") (pinfunction "S_3") (pintype "passive"))
      (node (ref "PRECHARGE/AIRS") (pin "4") (pinfunction "S_4") (pintype "passive"))
      (node (ref "PRECHARGE/AIRS") (pin "6") (pinfunction "S_6") (pintype "passive"))
      (node (ref "Q1") (pin "2") (pinfunction "S_2") (pintype "passive"))
      (node (ref "Q2") (pin "2") (pinfunction "S_2") (pintype "passive"))
      (node (ref "Q3") (pin "2") (pinfunction "S_2") (pintype "passive"))
      (node (ref "Q4") (pin "2") (pinfunction "S_2") (pintype "passive"))
      (node (ref "R11") (pin "1") (pinfunction "1_1") (pintype "passive"))
      (node (ref "R12") (pin "1") (pinfunction "1_1") (pintype "passive"))
      (node (ref "R19") (pin "1") (pinfunction "1_1") (pintype "passive"))
      (node (ref "R24") (pin "1") (pinfunction "1_1") (pintype "passive"))
      (node (ref "R25") (pin "1") (pinfunction "1_1") (pintype "passive"))
      (node (ref "R3") (pin "2") (pinfunction "2_2") (pintype "passive"))
      (node (ref "R9") (pin "1") (pinfunction "1_1") (pintype "passive"))
      (node (ref "THERMAL_EX_I/0") (pin "8") (pinfunction "8_8") (pintype "passive"))
      (node (ref "TP24") (pin "TP") (pinfunction "TP_TP") (pintype "input"))
      (node (ref "WIFI_MODULE") (pin "8") (pinfunction "8_8") (pintype "passive"))
    )
    (net (code "15") (name "HIGHEST_TEMP") (class "Default")
      (node (ref "THERMAL_EX_I/0") (pin "4") (pinfunction "4_4") (pintype "passive"))
      (node (ref "TP9") (pin "TP") (pinfunction "PP_TP") (pintype "input"))
    )
    (net (code "16") (name "IMD_LED") (class "Default")
      (node (ref "MISC_I/O") (pin "3") (pinfunction "3_3") (pintype "passive"))
    )
    (net (code "17") (name "IMD_LED-") (class "Default")
      (node (ref "Q3") (pin "3") (pinfunction "D_3") (pintype "passive"))
    )
    (net (code "18") (name "LOWEST_TEMP") (class "Default")
      (node (ref "THERMAL_EX_I/0") (pin "6") (pinfunction "6_6") (pintype "passive"))
      (node (ref "TP8") (pin "TP") (pinfunction "PP_TP") (pintype "input"))
    )
    (net (code "19") (name "M_HS") (class "Default")
      (node (ref "ISOMETER_I/O") (pin "5") (pinfunction "5_5") (pintype "passive"))
    )
    (net (code "20") (name "Net-(EMSDCB-S)") (class "Default")
      (node (ref "EMSDC") (pin "2") (pinfunction "S_2") (pintype "passive"))
      (node (ref "K7") (pin "4") (pinfunction "NO_4") (pintype "bidirectional"))
    )
    (net (code "21") (name "Net-(EMSDCC-S)") (class "Default")
      (node (ref "EMSDC") (pin "3") (pinfunction "S_3") (pintype "passive"))
      (node (ref "EMSDC") (pin "4") (pinfunction "S_4") (pintype "passive"))
    )
    (net (code "22") (name "Net-(EMSDCE-S)") (class "Default")
      (node (ref "EMSDC") (pin "5") (pinfunction "S_5") (pintype "passive"))
      (node (ref "K2") (pin "1") (pinfunction "1_1") (pintype "bidirectional"))
      (node (ref "PRECHARGE/AIRS") (pin "5") (pinfunction "S_5") (pintype "passive"))
    )
    (net (code "23") (name "Net-(FANA-S)") (class "Default")
      (node (ref "FAN") (pin "1") (pinfunction "S_1") (pintype "passive"))
      (node (ref "K3") (pin "4") (pinfunction "NO_4") (pintype "bidirectional"))
    )
    (net (code "24") (name "Net-(IC1A-Q0)") (class "Default")
      (node (ref "IC1") (pin "2") (pinfunction "Q0_2") (pintype "output"))
      (node (ref "IC9") (pin "1") (pinfunction "I0_1") (pintype "input"))
      (node (ref "IC9") (pin "2") (pinfunction "I1_2") (pintype "input"))
      (node (ref "Q3") (pin "1") (pinfunction "G_1") (pintype "passive"))
      (node (ref "R25") (pin "2") (pinfunction "2_2") (pintype "passive"))
      (node (ref "TP5") (pin "TP") (pinfunction "TP_TP") (pintype "input"))
    )
    (net (code "25") (name "Net-(IC1A-S0)") (class "Default")
      (node (ref "IC1") (pin "4") (pinfunction "S0_4") (pintype "input"))
      (node (ref "LED6") (pin "C") (pinfunction "C_C") (pintype "passive"))
      (node (ref "OK2") (pin "6") (pinfunction "VO_6") (pintype "passive"))
      (node (ref "TP1") (pin "TP") (pinfunction "TP_TP") (pintype "input"))
    )
    (net (code "26") (name "Net-(IC1A-S1)") (class "Default")
      (node (ref "C9") (pin "1") (pinfunction "1_1") (pintype "passive"))
      (node (ref "IC1") (pin "6") (pinfunction "S1_6") (pintype "input"))
      (node (ref "R2") (pin "2") (pinfunction "2_2") (pintype "passive"))
      (node (ref "TP12") (pin "TP") (pinfunction "TP_TP") (pintype "input"))
    )
    (net (code "27") (name "Net-(IC2-CV)") (class "Default")
      (node (ref "C6") (pin "1") (pinfunction "1_1") (pintype "passive"))
      (node (ref "IC2") (pin "5") (pinfunction "CV_5") (pintype "input"))
    )
    (net (code "28") (name "Net-(IC2-DIS)") (class "Default")
      (node (ref "C7") (pin "1") (pinfunction "1_1") (pintype "passive"))
      (node (ref "IC2") (pin "6") (pinfunction "THR_6") (pintype "input"))
      (node (ref "IC2") (pin "7") (pinfunction "DIS_7") (pintype "input"))
      (node (ref "R5") (pin "1") (pinfunction "1_1") (pintype "passive"))
    )
    (net (code "29") (name "Net-(IC2-TR)") (class "Default")
      (node (ref "C8") (pin "1") (pinfunction "1_1") (pintype "passive"))
      (node (ref "IC2") (pin "2") (pinfunction "TR_2") (pintype "input"))
      (node (ref "R10") (pin "1") (pinfunction "1_1") (pintype "passive"))
      (node (ref "R11") (pin "2") (pinfunction "2_2") (pintype "passive"))
    )
    (net (code "30") (name "Net-(IC9A-O)") (class "Default")
      (node (ref "IC9") (pin "3") (pinfunction "O_3") (pintype "output"))
      (node (ref "Q2") (pin "1") (pinfunction "G_1") (pintype "passive"))
      (node (ref "R24") (pin "2") (pinfunction "2_2") (pintype "passive"))
      (node (ref "TP17") (pin "TP") (pinfunction "TP_TP") (pintype "input"))
    )
    (net (code "31") (name "Net-(IC9B-O)") (class "Default")
      (node (ref "IC9") (pin "4") (pinfunction "O_4") (pintype "output"))
      (node (ref "Q4") (pin "1") (pinfunction "G_1") (pintype "passive"))
      (node (ref "R19") (pin "2") (pinfunction "2_2") (pintype "passive"))
      (node (ref "TP2") (pin "TP") (pinfunction "TP_TP") (pintype "input"))
    )
    (net (code "32") (name "Net-(IC9C-I0)") (class "Default")
      (node (ref "IC9") (pin "11") (pinfunction "O_11") (pintype "output"))
      (node (ref "IC9") (pin "8") (pinfunction "I0_8") (pintype "input"))
      (node (ref "IC9") (pin "9") (pinfunction "I1_9") (pintype "input"))
      (node (ref "TP11") (pin "TP") (pinfunction "TP_TP") (pintype "input"))
    )
    (net (code "33") (name "Net-(IC9C-O)") (class "Default")
      (node (ref "IC9") (pin "10") (pinfunction "O_10") (pintype "output"))
      (node (ref "R2") (pin "1") (pinfunction "1_1") (pintype "passive"))
      (node (ref "TP16") (pin "TP") (pinfunction "TP_TP") (pintype "input"))
    )
    (net (code "34") (name "Net-(K6-COIL_2)") (class "Default")
      (node (ref "D7") (pin "A") (pinfunction "A_A") (pintype "passive"))
      (node (ref "K6") (pin "2") (pinfunction "COIL_2_2") (pintype "bidirectional"))
      (node (ref "LED7") (pin "C") (pinfunction "C_C") (pintype "passive"))
      (node (ref "Q4") (pin "3") (pinfunction "D_3") (pintype "passive"))
      (node (ref "TP21") (pin "TP") (pinfunction "TP_TP") (pintype "input"))
    )
    (net (code "35") (name "Net-(K6-NO)") (class "Default")
      (node (ref "K6") (pin "4") (pinfunction "NO_4") (pintype "bidirectional"))
      (node (ref "K7") (pin "3") (pinfunction "COM_3") (pintype "bidirectional"))
    )
    (net (code "36") (name "Net-(K7-COIL_2)") (class "Default")
      (node (ref "D8") (pin "A") (pinfunction "A_A") (pintype "passive"))
      (node (ref "K7") (pin "2") (pinfunction "COIL_2_2") (pintype "bidirectional"))
      (node (ref "LED8") (pin "C") (pinfunction "C_C") (pintype "passive"))
      (node (ref "Q2") (pin "3") (pinfunction "D_3") (pintype "passive"))
      (node (ref "TP14") (pin "TP") (pinfunction "TP_TP") (pintype "input"))
    )
    (net (code "37") (name "Net-(LED1-PadA)") (class "Default")
      (node (ref "LED1") (pin "A") (pinfunction "A_A") (pintype "passive"))
      (node (ref "R20") (pin "2") (pinfunction "2_2") (pintype "passive"))
    )
    (net (code "38") (name "Net-(LED2-PadA)") (class "Default")
      (node (ref "LED2") (pin "A") (pinfunction "A_A") (pintype "passive"))
      (node (ref "R21") (pin "2") (pinfunction "2_2") (pintype "passive"))
    )
    (net (code "39") (name "Net-(LED3-PadA)") (class "Default")
      (node (ref "LED3") (pin "A") (pinfunction "A_A") (pintype "passive"))
      (node (ref "R22") (pin "2") (pinfunction "2_2") (pintype "passive"))
    )
    (net (code "40") (name "Net-(LED4-PadA)") (class "Default")
      (node (ref "LED4") (pin "A") (pinfunction "A_A") (pintype "passive"))
      (node (ref "R7") (pin "2") (pinfunction "2_2") (pintype "passive"))
    )
    (net (code "41") (name "Net-(LED5-PadA)") (class "Default")
      (node (ref "LED5") (pin "A") (pinfunction "A_A") (pintype "passive"))
      (node (ref "R6") (pin "2") (pinfunction "2_2") (pintype "passive"))
    )
    (net (code "42") (name "Net-(LED6-PadA)") (class "Default")
      (node (ref "LED6") (pin "A") (pinfunction "A_A") (pintype "passive"))
      (node (ref "R8") (pin "2") (pinfunction "2_2") (pintype "passive"))
    )
    (net (code "43") (name "Net-(LED7-PadA)") (class "Default")
      (node (ref "LED7") (pin "A") (pinfunction "A_A") (pintype "passive"))
      (node (ref "R14") (pin "1") (pinfunction "1_1") (pintype "passive"))
    )
    (net (code "44") (name "Net-(LED8-PadA)") (class "Default")
      (node (ref "LED8") (pin "A") (pinfunction "A_A") (pintype "passive"))
      (node (ref "R15") (pin "1") (pinfunction "1_1") (pintype "passive"))
    )
    (net (code "45") (name "Net-(OK2-C)") (class "Default")
      (node (ref "OK2") (pin "3") (pinfunction "C_3") (pintype "passive"))
      (node (ref "R3") (pin "1") (pinfunction "1_1") (pintype "passive"))
    )
    (net (code "46") (name "Net-(POWER/GNDA-S)") (class "Default")
      (node (ref "F1") (pin "2") (pinfunction "2_2") (pintype "bidirectional"))
      (node (ref "POWER/GND") (pin "1") (pinfunction "S_1") (pintype "passive"))
    )
    (net (code "47") (name "Net-(POWER/GNDB-S)") (class "Default")
      (node (ref "F2") (pin "2") (pinfunction "2_2") (pintype "bidirectional"))
      (node (ref "POWER/GND") (pin "2") (pinfunction "S_2") (pintype "passive"))
    )
    (net (code "48") (name "Net-(PRECHARGE/AIRSA-S)") (class "Default")
      (node (ref "K2") (pin "2") (pinfunction "2_2") (pintype "bidirectional"))
      (node (ref "PRECHARGE/AIRS") (pin "1") (pinfunction "S_1") (pintype "passive"))
    )
    (net (code "49") (name "Net-(PRECHARGE/AIRSB-S)") (class "Default")
      (node (ref "K2") (pin "3") (pinfunction "3_3") (pintype "bidirectional"))
      (node (ref "PRECHARGE/AIRS") (pin "2") (pinfunction "S_2") (pintype "passive"))
    )
    (net (code "50") (name "OK_HS") (class "Default")
      (node (ref "ISOMETER_I/O") (pin "8") (pinfunction "8_8") (pintype "passive"))
      (node (ref "OK2") (pin "2") (pinfunction "A_2") (pintype "passive"))
      (node (ref "TP10") (pin "TP") (pinfunction "TP_TP") (pintype "input"))
    )
    (net (code "51") (name "PRECHARGE_EMSDC1") (class "Default")
      (node (ref "K6") (pin "3") (pinfunction "COM_3") (pintype "bidirectional"))
      (node (ref "PRECHARGE") (pin "1") (pinfunction "1_1") (pintype "passive"))
    )
    (net (code "52") (name "PRECHARGE_EMSDC2") (class "Default")
      (node (ref "EMSDC") (pin "1") (pinfunction "S_1") (pintype "passive"))
      (node (ref "PRECHARGE") (pin "2") (pinfunction "2_2") (pintype "passive"))
    )
    (net (code "53") (name "PRECHARGE_SELECT") (class "Default")
      (node (ref "BMS_I/O") (pin "7") (pinfunction "7_7") (pintype "passive"))
      (node (ref "D1") (pin "A") (pinfunction "A_A") (pintype "passive"))
      (node (ref "K2") (pin "5") (pinfunction "5_5") (pintype "bidirectional"))
      (node (ref "LED1") (pin "C") (pinfunction "C_C") (pintype "passive"))
      (node (ref "PRECHARGE") (pin "3") (pinfunction "3_3") (pintype "passive"))
      (node (ref "TP23") (pin "TP") (pinfunction "TP_TP") (pintype "input"))
    )
    (net (code "54") (name "READY_POWER") (class "Default")
      (node (ref "BMS_POWER/GND") (pin "1") (pinfunction "S_1") (pintype "passive"))
      (node (ref "D2") (pin "2") (pinfunction "A_2") (pintype "bidirectional"))
      (node (ref "F2") (pin "1") (pinfunction "1_1") (pintype "bidirectional"))
      (node (ref "PRECHARGE") (pin "8") (pinfunction "8_8") (pintype "passive"))
      (node (ref "THERMAL_EX_I/0") (pin "1") (pinfunction "1_1") (pintype "passive"))
      (node (ref "WIFI_MODULE") (pin "1") (pinfunction "1_1") (pintype "passive"))
    )
    (net (code "55") (name "STARTUP_RESET") (class "Default")
      (node (ref "IC1") (pin "3") (pinfunction "R0_3") (pintype "input"))
      (node (ref "IC1") (pin "7") (pinfunction "R1_7") (pintype "input"))
      (node (ref "IC2") (pin "3") (pinfunction "Q_3") (pintype "output"))
      (node (ref "R9") (pin "2") (pinfunction "2_2") (pintype "passive"))
      (node (ref "TP4") (pin "TP") (pinfunction "TP_TP") (pintype "input"))
    )
    (net (code "56") (name "unconnected-(CAN1-Pad1)") (class "Default")
      (node (ref "CAN1") (pin "1") (pinfunction "1_1") (pintype "bidirectional"))
    )
    (net (code "57") (name "unconnected-(CAN1-Pad2)") (class "Default")
      (node (ref "CAN1") (pin "2") (pinfunction "2_2") (pintype "bidirectional"))
    )
    (net (code "58") (name "unconnected-(CAN1-Pad4)") (class "Default")
      (node (ref "CAN1") (pin "4") (pinfunction "4_4") (pintype "bidirectional"))
    )
    (net (code "59") (name "unconnected-(CAN1-Pad6)") (class "Default")
      (node (ref "CAN1") (pin "6") (pinfunction "6_6") (pintype "bidirectional"))
    )
    (net (code "60") (name "unconnected-(CAN1-Pad7)") (class "Default")
      (node (ref "CAN1") (pin "7") (pinfunction "7_7") (pintype "bidirectional"))
    )
    (net (code "61") (name "unconnected-(CAN1-Pad8)") (class "Default")
      (node (ref "CAN1") (pin "8") (pinfunction "8_8") (pintype "bidirectional"))
    )
    (net (code "62") (name "unconnected-(CAN1-Pad9)") (class "Default")
      (node (ref "CAN1") (pin "9") (pinfunction "9_9") (pintype "bidirectional"))
    )
    (net (code "63") (name "unconnected-(CAN1-PadMH1)") (class "Default")
      (node (ref "CAN1") (pin "MH1") (pinfunction "MH1_MH1") (pintype "bidirectional"))
    )
    (net (code "64") (name "unconnected-(CAN1-PadMH2)") (class "Default")
      (node (ref "CAN1") (pin "MH2") (pinfunction "MH2_MH2") (pintype "bidirectional"))
    )
    (net (code "65") (name "unconnected-(CAN2-Pad1)") (class "Default")
      (node (ref "CAN2") (pin "1") (pinfunction "1_1") (pintype "bidirectional"))
    )
    (net (code "66") (name "unconnected-(CAN2-Pad2)") (class "Default")
      (node (ref "CAN2") (pin "2") (pinfunction "2_2") (pintype "bidirectional"))
    )
    (net (code "67") (name "unconnected-(CAN2-Pad4)") (class "Default")
      (node (ref "CAN2") (pin "4") (pinfunction "4_4") (pintype "bidirectional"))
    )
    (net (code "68") (name "unconnected-(CAN2-Pad6)") (class "Default")
      (node (ref "CAN2") (pin "6") (pinfunction "6_6") (pintype "bidirectional"))
    )
    (net (code "69") (name "unconnected-(CAN2-Pad7)") (class "Default")
      (node (ref "CAN2") (pin "7") (pinfunction "7_7") (pintype "bidirectional"))
    )
    (net (code "70") (name "unconnected-(CAN2-Pad8)") (class "Default")
      (node (ref "CAN2") (pin "8") (pinfunction "8_8") (pintype "bidirectional"))
    )
    (net (code "71") (name "unconnected-(CAN2-Pad9)") (class "Default")
      (node (ref "CAN2") (pin "9") (pinfunction "9_9") (pintype "bidirectional"))
    )
    (net (code "72") (name "unconnected-(CAN2-PadMH1)") (class "Default")
      (node (ref "CAN2") (pin "MH1") (pinfunction "MH1_MH1") (pintype "bidirectional"))
    )
    (net (code "73") (name "unconnected-(CAN2-PadMH2)") (class "Default")
      (node (ref "CAN2") (pin "MH2") (pinfunction "MH2_MH2") (pintype "bidirectional"))
    )
    (net (code "74") (name "unconnected-(EMSDC1A-S-Pad1)") (class "Default")
      (node (ref "EMSDC1") (pin "1") (pinfunction "S_1") (pintype "passive"))
    )
    (net (code "75") (name "unconnected-(EMSDC1B-S-Pad2)") (class "Default")
      (node (ref "EMSDC1") (pin "2") (pinfunction "S_2") (pintype "passive"))
    )
    (net (code "76") (name "unconnected-(EMSDC1C-S-Pad3)") (class "Default")
      (node (ref "EMSDC1") (pin "3") (pinfunction "S_3") (pintype "passive"))
    )
    (net (code "77") (name "unconnected-(EMSDC1D-S-Pad4)") (class "Default")
      (node (ref "EMSDC1") (pin "4") (pinfunction "S_4") (pintype "passive"))
    )
    (net (code "78") (name "unconnected-(EMSDC1E-S-Pad5)") (class "Default")
      (node (ref "EMSDC1") (pin "5") (pinfunction "S_5") (pintype "passive"))
    )
    (net (code "79") (name "unconnected-(EMSDC1F-S-Pad6)") (class "Default")
      (node (ref "EMSDC1") (pin "6") (pinfunction "S_6") (pintype "passive"))
    )
    (net (code "80") (name "unconnected-(IC1A-Q2-Pad10)") (class "Default")
      (node (ref "IC1") (pin "10") (pinfunction "Q2_10") (pintype "output"))
    )
    (net (code "81") (name "unconnected-(IC1A-Q3-Pad1)") (class "Default")
      (node (ref "IC1") (pin "1") (pinfunction "Q3_1") (pintype "output"))
    )
    (net (code "82") (name "unconnected-(IC4A-~{SHDN}-Pad5)") (class "Default")
      (node (ref "IC4") (pin "5") (pinfunction "~{SHDN}_5") (pintype "input"))
    )
    (net (code "83") (name "unconnected-(ISOMETER_I/O-Pad4)") (class "Default")
      (node (ref "ISOMETER_I/O") (pin "4") (pinfunction "4_4") (pintype "passive"))
    )
    (net (code "84") (name "unconnected-(ISOMETER_I/O-Pad6)") (class "Default")
      (node (ref "ISOMETER_I/O") (pin "6") (pinfunction "6_6") (pintype "passive"))
    )
    (net (code "85") (name "unconnected-(ISOMETER_I/O-Pad7)") (class "Default")
      (node (ref "ISOMETER_I/O") (pin "7") (pinfunction "7_7") (pintype "passive"))
    )
    (net (code "86") (name "unconnected-(THERMAL_EX_I/0-Pad7)") (class "Default")
      (node (ref "THERMAL_EX_I/0") (pin "7") (pinfunction "7_7") (pintype "passive"))
    )
    (net (code "87") (name "unconnected-(WIFI_MODULE-Pad4)") (class "Default")
      (node (ref "WIFI_MODULE") (pin "4") (pinfunction "4_4") (pintype "passive"))
    )
    (net (code "88") (name "unconnected-(WIFI_MODULE-Pad6)") (class "Default")
      (node (ref "WIFI_MODULE") (pin "6") (pinfunction "6_6") (pintype "passive"))
    )
    (net (code "89") (name "unconnected-(WIFI_MODULE-Pad7)") (class "Default")
      (node (ref "WIFI_MODULE") (pin "7") (pinfunction "7_7") (pintype "passive"))
    )
  )
)
